# DebuggerMCU.net
KiCad netlist of a schematic drawn in Altium Designer
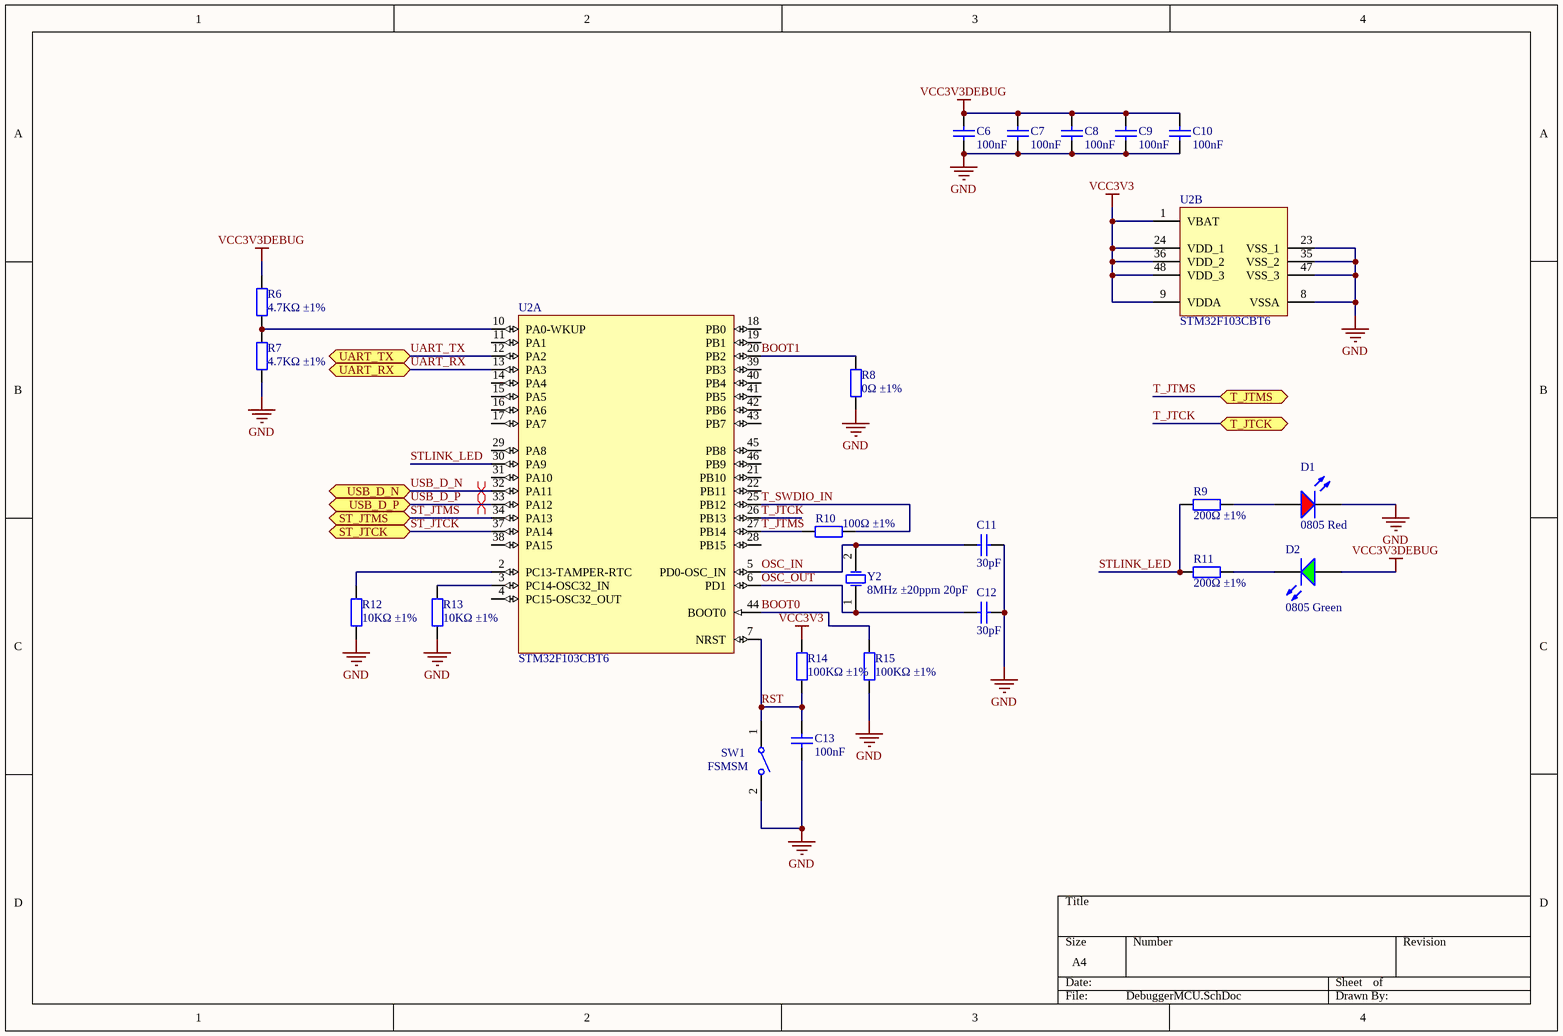
[diagram p0: DebuggerMCU.SchDoc]

(export (version "E")
  (design (tool "Eeschema 10.0.6"))
  (components
    (comp (ref "C6")
      (value "100nF")
      (footprint "0402_C")
      (description "Chip capacitors")
      (fields
        (field (name "MANUFACTURER") "Samsung Electro-Mechanics")
        (field (name "PARTNUMBER") "CL05B104KO5NNNC")
      )
      (libsource (lib "Miscellaneous Devices LC") (part "0402 100nF (104) 10% 16V"))
    )
    (comp (ref "C7")
      (value "100nF")
      (footprint "0402_C")
      (description "Chip capacitors")
      (fields
        (field (name "MANUFACTURER") "Samsung Electro-Mechanics")
        (field (name "PARTNUMBER") "CL05B104KO5NNNC")
      )
      (libsource (lib "Miscellaneous Devices LC") (part "0402 100nF (104) 10% 16V"))
    )
    (comp (ref "C8")
      (value "100nF")
      (footprint "0402_C")
      (description "Chip capacitors")
      (fields
        (field (name "MANUFACTURER") "Samsung Electro-Mechanics")
        (field (name "PARTNUMBER") "CL05B104KO5NNNC")
      )
      (libsource (lib "Miscellaneous Devices LC") (part "0402 100nF (104) 10% 16V"))
    )
    (comp (ref "C9")
      (value "100nF")
      (footprint "0402_C")
      (description "Chip capacitors")
      (fields
        (field (name "MANUFACTURER") "Samsung Electro-Mechanics")
        (field (name "PARTNUMBER") "CL05B104KO5NNNC")
      )
      (libsource (lib "Miscellaneous Devices LC") (part "0402 100nF (104) 10% 16V"))
    )
    (comp (ref "C10")
      (value "100nF")
      (footprint "0402_C")
      (description "Chip capacitors")
      (fields
        (field (name "MANUFACTURER") "Samsung Electro-Mechanics")
        (field (name "PARTNUMBER") "CL05B104KO5NNNC")
      )
      (libsource (lib "Miscellaneous Devices LC") (part "0402 100nF (104) 10% 16V"))
    )
    (comp (ref "C11")
      (value "30pF")
      (footprint "0402_C")
      (description "Chip capacitors")
      (fields
        (field (name "MANUFACTURER") "Guangdong Fenghua Advanced Tech")
        (field (name "PARTNUMBER") "0402CG300J500NT")
      )
      (libsource (lib "Miscellaneous Devices LC") (part "0402 30pF (300) 5% 50V"))
    )
    (comp (ref "C12")
      (value "30pF")
      (footprint "0402_C")
      (description "Chip capacitors")
      (fields
        (field (name "MANUFACTURER") "Guangdong Fenghua Advanced Tech")
        (field (name "PARTNUMBER") "0402CG300J500NT")
      )
      (libsource (lib "Miscellaneous Devices LC") (part "0402 30pF (300) 5% 50V"))
    )
    (comp (ref "C13")
      (value "100nF")
      (footprint "0402_C")
      (description "Chip capacitors")
      (fields
        (field (name "MANUFACTURER") "Samsung Electro-Mechanics")
        (field (name "PARTNUMBER") "CL05B104KO5NNNC")
      )
      (libsource (lib "Miscellaneous Devices LC") (part "0402 100nF (104) 10% 16V"))
    )
    (comp (ref "D1")
      (value "0805 Red")
      (footprint "0805_LED_S1")
      (description "LED")
      (libsource (lib "Miscellaneous Devices LC") (part "0805 LED Red"))
    )
    (comp (ref "D2")
      (value "0805 Green")
      (footprint "0805_LED_S1")
      (description "LED")
      (libsource (lib "Miscellaneous Devices LC") (part "0805 LED Green"))
    )
    (comp (ref "R6")
      (value "4.7KΩ ±1%")
      (footprint "0805_R")
      (description "Chip resistor")
      (fields (field (name "MANUFACTURER") "Uniroyal Elec") (field (name "POWER") "1/8W"))
      (libsource (lib "Miscellaneous Devices LC") (part "0805 4.7K (4701) 1%"))
    )
    (comp (ref "R7")
      (value "4.7KΩ ±1%")
      (footprint "0805_R")
      (description "Chip resistor")
      (fields (field (name "MANUFACTURER") "Uniroyal Elec") (field (name "POWER") "1/8W"))
      (libsource (lib "Miscellaneous Devices LC") (part "0805 4.7K (4701) 1%"))
    )
    (comp (ref "R8")
      (value "0Ω ±1%")
      (footprint "0402_R")
      (description "Chip resistor")
      (fields (field (name "POWER") "1/16W") (field (name "MANUFACTURER") "Uniroyal Elec"))
      (libsource (lib "Miscellaneous Devices LC") (part "0402 0R (0R0) 1%"))
    )
    (comp (ref "R9")
      (value "200Ω ±1%")
      (footprint "0402_R")
      (description "Chip resistor")
      (fields (field (name "MANUFACTURER") "Uniroyal Elec") (field (name "PARTNUMBER") "0402WGF2000TCE"))
      (libsource (lib "Miscellaneous Devices LC") (part "0402 200R (2000) 1%"))
    )
    (comp (ref "R10")
      (value "100Ω ±1%")
      (footprint "0402_R")
      (description "Chip resistor")
      (fields (field (name "MANUFACTURER") "Uniroyal Elec") (field (name "PARTNUMBER") "0402WGF1000TCE"))
      (libsource (lib "Miscellaneous Devices LC") (part "0402 100R (1000) 1%"))
    )
    (comp (ref "R11")
      (value "200Ω ±1%")
      (footprint "0402_R")
      (description "Chip resistor")
      (fields (field (name "MANUFACTURER") "Uniroyal Elec") (field (name "PARTNUMBER") "0402WGF2000TCE"))
      (libsource (lib "Miscellaneous Devices LC") (part "0402 200R (2000) 1%"))
    )
    (comp (ref "R12")
      (value "10KΩ ±1%")
      (footprint "0402_R")
      (description "Chip resistor")
      (fields (field (name "MANUFACTURER") "Uniroyal Elec") (field (name "PARTNUMBER") "0402WGF1002TCE"))
      (libsource (lib "Miscellaneous Devices LC") (part "0402 10K (1002) 1%"))
    )
    (comp (ref "R13")
      (value "10KΩ ±1%")
      (footprint "0402_R")
      (description "Chip resistor")
      (fields (field (name "MANUFACTURER") "Uniroyal Elec") (field (name "PARTNUMBER") "0402WGF1002TCE"))
      (libsource (lib "Miscellaneous Devices LC") (part "0402 10K (1002) 1%"))
    )
    (comp (ref "R14")
      (value "100KΩ ±1%")
      (footprint "0402_R")
      (description "Chip resistor")
      (fields (field (name "MANUFACTURER") "Uniroyal Elec") (field (name "PARTNUMBER") "0402WGF1003TCE"))
      (libsource (lib "Miscellaneous Devices LC") (part "0402 100K (1003) 1%"))
    )
    (comp (ref "R15")
      (value "100KΩ ±1%")
      (footprint "0402_R")
      (description "Chip resistor")
      (fields (field (name "MANUFACTURER") "Uniroyal Elec") (field (name "PARTNUMBER") "0402WGF1003TCE"))
      (libsource (lib "Miscellaneous Devices LC") (part "0402 100K (1003) 1%"))
    )
    (comp (ref "SW1")
      (value "FSMSM")
      (footprint "TECO-FSMSM-2_V")
      (description "FSMSM Push Button Switch, 50 mA, -35 to 85 degC, 2-Pin SMD, RoHS, Bulk")
      (fields (field (name "MANUFACTURER") "TE Connectivity"))
      (libsource (lib "Altium Content Vault") (part "SW-SPST-2_C"))
    )
    (comp (ref "U2")
      (value "STM32F103CBT6")
      (footprint "LQFP-48_7x7x05P")
      (description "ARM")
      (libsource (lib "Miscellaneous Devices LC") (part "STM32F103CBT6"))
    )
    (comp (ref "Y2")
      (value "8MHz ±20ppm 20pF")
      (footprint "SMD-5032_2P")
      (description "贴片晶振")
      (libsource (lib "Miscellaneous Devices LC") (part "SMD-5032_2P 8MHz 20ppm 20pF"))
    )
  )
  (nets
    (net (code "1") (name "/BOOT0") (class "Default")
      (node (ref "R15") (pin "2") (pinfunction "2_2") (pintype "passive"))
      (node (ref "U2") (pin "44") (pinfunction "BOOT0_44") (pintype "input"))
    )
    (net (code "2") (name "/BOOT1") (class "Default")
      (node (ref "R8") (pin "2") (pinfunction "2_2") (pintype "passive"))
      (node (ref "U2") (pin "20") (pinfunction "PB2_20") (pintype "bidirectional"))
    )
    (net (code "3") (name "/OSC_IN") (class "Default")
      (node (ref "C11") (pin "1") (pinfunction "1_1") (pintype "passive"))
      (node (ref "U2") (pin "5") (pinfunction "PD0-OSC_IN_5") (pintype "bidirectional"))
      (node (ref "Y2") (pin "2") (pinfunction "OSC2_2") (pintype "passive"))
    )
    (net (code "4") (name "/OSC_OUT") (class "Default")
      (node (ref "C12") (pin "1") (pinfunction "1_1") (pintype "passive"))
      (node (ref "U2") (pin "6") (pinfunction "PD1_6") (pintype "bidirectional"))
      (node (ref "Y2") (pin "1") (pinfunction "OSC1_1") (pintype "passive"))
    )
    (net (code "5") (name "/RST") (class "Default")
      (node (ref "C13") (pin "2") (pinfunction "2_2") (pintype "passive"))
      (node (ref "R14") (pin "1") (pinfunction "1_1") (pintype "passive"))
      (node (ref "SW1") (pin "1") (pinfunction "1_1") (pintype "passive"))
      (node (ref "U2") (pin "7") (pinfunction "NRST_7") (pintype "bidirectional"))
    )
    (net (code "6") (name "/STLINK_LED") (class "Default")
      (node (ref "R11") (pin "1") (pinfunction "1_1") (pintype "passive"))
      (node (ref "R9") (pin "1") (pinfunction "1_1") (pintype "passive"))
      (node (ref "U2") (pin "30") (pinfunction "PA9_30") (pintype "bidirectional"))
    )
    (net (code "7") (name "/ST_JTCK") (class "Default")
      (node (ref "U2") (pin "37") (pinfunction "PA14_37") (pintype "bidirectional"))
    )
    (net (code "8") (name "/ST_JTMS") (class "Default")
      (node (ref "U2") (pin "34") (pinfunction "PA13_34") (pintype "bidirectional"))
    )
    (net (code "9") (name "/T_JTCK") (class "Default")
      (node (ref "U2") (pin "26") (pinfunction "PB13_26") (pintype "bidirectional"))
    )
    (net (code "10") (name "/T_JTMS") (class "Default")
      (node (ref "R10") (pin "2") (pinfunction "2_2") (pintype "passive"))
      (node (ref "U2") (pin "27") (pinfunction "PB14_27") (pintype "bidirectional"))
    )
    (net (code "11") (name "/T_SWDIO_IN") (class "Default")
      (node (ref "R10") (pin "1") (pinfunction "1_1") (pintype "passive"))
      (node (ref "U2") (pin "25") (pinfunction "PB12_25") (pintype "bidirectional"))
    )
    (net (code "12") (name "/UART_RX") (class "Default")
      (node (ref "U2") (pin "13") (pinfunction "PA3_13") (pintype "bidirectional"))
    )
    (net (code "13") (name "/UART_TX") (class "Default")
      (node (ref "U2") (pin "12") (pinfunction "PA2_12") (pintype "bidirectional"))
    )
    (net (code "14") (name "/USB_D_N") (class "Default")
      (node (ref "U2") (pin "32") (pinfunction "PA11_32") (pintype "bidirectional"))
    )
    (net (code "15") (name "/USB_D_P") (class "Default")
      (node (ref "U2") (pin "33") (pinfunction "PA12_33") (pintype "bidirectional"))
    )
    (net (code "16") (name "GND") (class "Default")
      (node (ref "C10") (pin "1") (pinfunction "1_1") (pintype "passive"))
      (node (ref "C11") (pin "2") (pinfunction "2_2") (pintype "passive"))
      (node (ref "C12") (pin "2") (pinfunction "2_2") (pintype "passive"))
      (node (ref "C13") (pin "1") (pinfunction "1_1") (pintype "passive"))
      (node (ref "C6") (pin "1") (pinfunction "1_1") (pintype "passive"))
      (node (ref "C7") (pin "1") (pinfunction "1_1") (pintype "passive"))
      (node (ref "C8") (pin "1") (pinfunction "1_1") (pintype "passive"))
      (node (ref "C9") (pin "1") (pinfunction "1_1") (pintype "passive"))
      (node (ref "D1") (pin "K") (pinfunction "K_K") (pintype "passive"))
      (node (ref "R12") (pin "1") (pinfunction "1_1") (pintype "passive"))
      (node (ref "R13") (pin "1") (pinfunction "1_1") (pintype "passive"))
      (node (ref "R15") (pin "1") (pinfunction "1_1") (pintype "passive"))
      (node (ref "R7") (pin "1") (pinfunction "1_1") (pintype "passive"))
      (node (ref "R8") (pin "1") (pinfunction "1_1") (pintype "passive"))
      (node (ref "SW1") (pin "2") (pinfunction "2_2") (pintype "passive"))
      (node (ref "U2") (pin "23") (pinfunction "VSS_1_23") (pintype "power_in"))
      (node (ref "U2") (pin "35") (pinfunction "VSS_2_35") (pintype "power_in"))
      (node (ref "U2") (pin "47") (pinfunction "VSS_3_47") (pintype "power_in"))
      (node (ref "U2") (pin "8") (pinfunction "VSSA_8") (pintype "power_in"))
    )
    (net (code "17") (name "Net-(D1-PadA)") (class "Default")
      (node (ref "D1") (pin "A") (pinfunction "A_A") (pintype "passive"))
      (node (ref "R9") (pin "2") (pinfunction "2_2") (pintype "passive"))
    )
    (net (code "18") (name "Net-(D2-PadK)") (class "Default")
      (node (ref "D2") (pin "K") (pinfunction "K_K") (pintype "passive"))
      (node (ref "R11") (pin "2") (pinfunction "2_2") (pintype "passive"))
    )
    (net (code "19") (name "Net-(U2A-PA0-WKUP)") (class "Default")
      (node (ref "R6") (pin "1") (pinfunction "1_1") (pintype "passive"))
      (node (ref "R7") (pin "2") (pinfunction "2_2") (pintype "passive"))
      (node (ref "U2") (pin "10") (pinfunction "PA0-WKUP_10") (pintype "bidirectional"))
    )
    (net (code "20") (name "Net-(U2A-PC13-TAMPER-RTC)") (class "Default")
      (node (ref "R12") (pin "2") (pinfunction "2_2") (pintype "passive"))
      (node (ref "U2") (pin "2") (pinfunction "PC13-TAMPER-RTC_2") (pintype "bidirectional"))
    )
    (net (code "21") (name "Net-(U2A-PC14-OSC32_IN)") (class "Default")
      (node (ref "R13") (pin "2") (pinfunction "2_2") (pintype "passive"))
      (node (ref "U2") (pin "3") (pinfunction "PC14-OSC32_IN_3") (pintype "bidirectional"))
    )
    (net (code "22") (name "VCC3V3") (class "Default")
      (node (ref "R14") (pin "2") (pinfunction "2_2") (pintype "passive"))
      (node (ref "U2") (pin "1") (pinfunction "VBAT_1") (pintype "power_in"))
      (node (ref "U2") (pin "24") (pinfunction "VDD_1_24") (pintype "power_in"))
      (node (ref "U2") (pin "36") (pinfunction "VDD_2_36") (pintype "power_in"))
      (node (ref "U2") (pin "48") (pinfunction "VDD_3_48") (pintype "power_in"))
      (node (ref "U2") (pin "9") (pinfunction "VDDA_9") (pintype "power_in"))
    )
    (net (code "23") (name "VCC3V3DEBUG") (class "Default")
      (node (ref "C10") (pin "2") (pinfunction "2_2") (pintype "passive"))
      (node (ref "C6") (pin "2") (pinfunction "2_2") (pintype "passive"))
      (node (ref "C7") (pin "2") (pinfunction "2_2") (pintype "passive"))
      (node (ref "C8") (pin "2") (pinfunction "2_2") (pintype "passive"))
      (node (ref "C9") (pin "2") (pinfunction "2_2") (pintype "passive"))
      (node (ref "D2") (pin "A") (pinfunction "A_A") (pintype "passive"))
      (node (ref "R6") (pin "2") (pinfunction "2_2") (pintype "passive"))
    )
    (net (code "24") (name "unconnected-(U2A-PA1-Pad11)") (class "Default")
      (node (ref "U2") (pin "11") (pinfunction "PA1_11") (pintype "bidirectional"))
    )
    (net (code "25") (name "unconnected-(U2A-PA4-Pad14)") (class "Default")
      (node (ref "U2") (pin "14") (pinfunction "PA4_14") (pintype "bidirectional"))
    )
    (net (code "26") (name "unconnected-(U2A-PA5-Pad15)") (class "Default")
      (node (ref "U2") (pin "15") (pinfunction "PA5_15") (pintype "bidirectional"))
    )
    (net (code "27") (name "unconnected-(U2A-PA6-Pad16)") (class "Default")
      (node (ref "U2") (pin "16") (pinfunction "PA6_16") (pintype "bidirectional"))
    )
    (net (code "28") (name "unconnected-(U2A-PA7-Pad17)") (class "Default")
      (node (ref "U2") (pin "17") (pinfunction "PA7_17") (pintype "bidirectional"))
    )
    (net (code "29") (name "unconnected-(U2A-PA8-Pad29)") (class "Default")
      (node (ref "U2") (pin "29") (pinfunction "PA8_29") (pintype "bidirectional"))
    )
    (net (code "30") (name "unconnected-(U2A-PA10-Pad31)") (class "Default")
      (node (ref "U2") (pin "31") (pinfunction "PA10_31") (pintype "bidirectional"))
    )
    (net (code "31") (name "unconnected-(U2A-PA15-Pad38)") (class "Default")
      (node (ref "U2") (pin "38") (pinfunction "PA15_38") (pintype "bidirectional"))
    )
    (net (code "32") (name "unconnected-(U2A-PB0-Pad18)") (class "Default")
      (node (ref "U2") (pin "18") (pinfunction "PB0_18") (pintype "bidirectional"))
    )
    (net (code "33") (name "unconnected-(U2A-PB1-Pad19)") (class "Default")
      (node (ref "U2") (pin "19") (pinfunction "PB1_19") (pintype "bidirectional"))
    )
    (net (code "34") (name "unconnected-(U2A-PB3-Pad39)") (class "Default")
      (node (ref "U2") (pin "39") (pinfunction "PB3_39") (pintype "bidirectional"))
    )
    (net (code "35") (name "unconnected-(U2A-PB4-Pad40)") (class "Default")
      (node (ref "U2") (pin "40") (pinfunction "PB4_40") (pintype "bidirectional"))
    )
    (net (code "36") (name "unconnected-(U2A-PB5-Pad41)") (class "Default")
      (node (ref "U2") (pin "41") (pinfunction "PB5_41") (pintype "bidirectional"))
    )
    (net (code "37") (name "unconnected-(U2A-PB6-Pad42)") (class "Default")
      (node (ref "U2") (pin "42") (pinfunction "PB6_42") (pintype "bidirectional"))
    )
    (net (code "38") (name "unconnected-(U2A-PB7-Pad43)") (class "Default")
      (node (ref "U2") (pin "43") (pinfunction "PB7_43") (pintype "bidirectional"))
    )
    (net (code "39") (name "unconnected-(U2A-PB8-Pad45)") (class "Default")
      (node (ref "U2") (pin "45") (pinfunction "PB8_45") (pintype "bidirectional"))
    )
    (net (code "40") (name "unconnected-(U2A-PB9-Pad46)") (class "Default")
      (node (ref "U2") (pin "46") (pinfunction "PB9_46") (pintype "bidirectional"))
    )
    (net (code "41") (name "unconnected-(U2A-PB10-Pad21)") (class "Default")
      (node (ref "U2") (pin "21") (pinfunction "PB10_21") (pintype "bidirectional"))
    )
    (net (code "42") (name "unconnected-(U2A-PB11-Pad22)") (class "Default")
      (node (ref "U2") (pin "22") (pinfunction "PB11_22") (pintype "bidirectional"))
    )
    (net (code "43") (name "unconnected-(U2A-PB15-Pad28)") (class "Default")
      (node (ref "U2") (pin "28") (pinfunction "PB15_28") (pintype "bidirectional"))
    )
    (net (code "44") (name "unconnected-(U2A-PC15-OSC32_OUT-Pad4)") (class "Default")
      (node (ref "U2") (pin "4") (pinfunction "PC15-OSC32_OUT_4") (pintype "bidirectional"))
    )
  )
)
